# panel3.net
KiCad netlist of a schematic drawn in Altium Designer
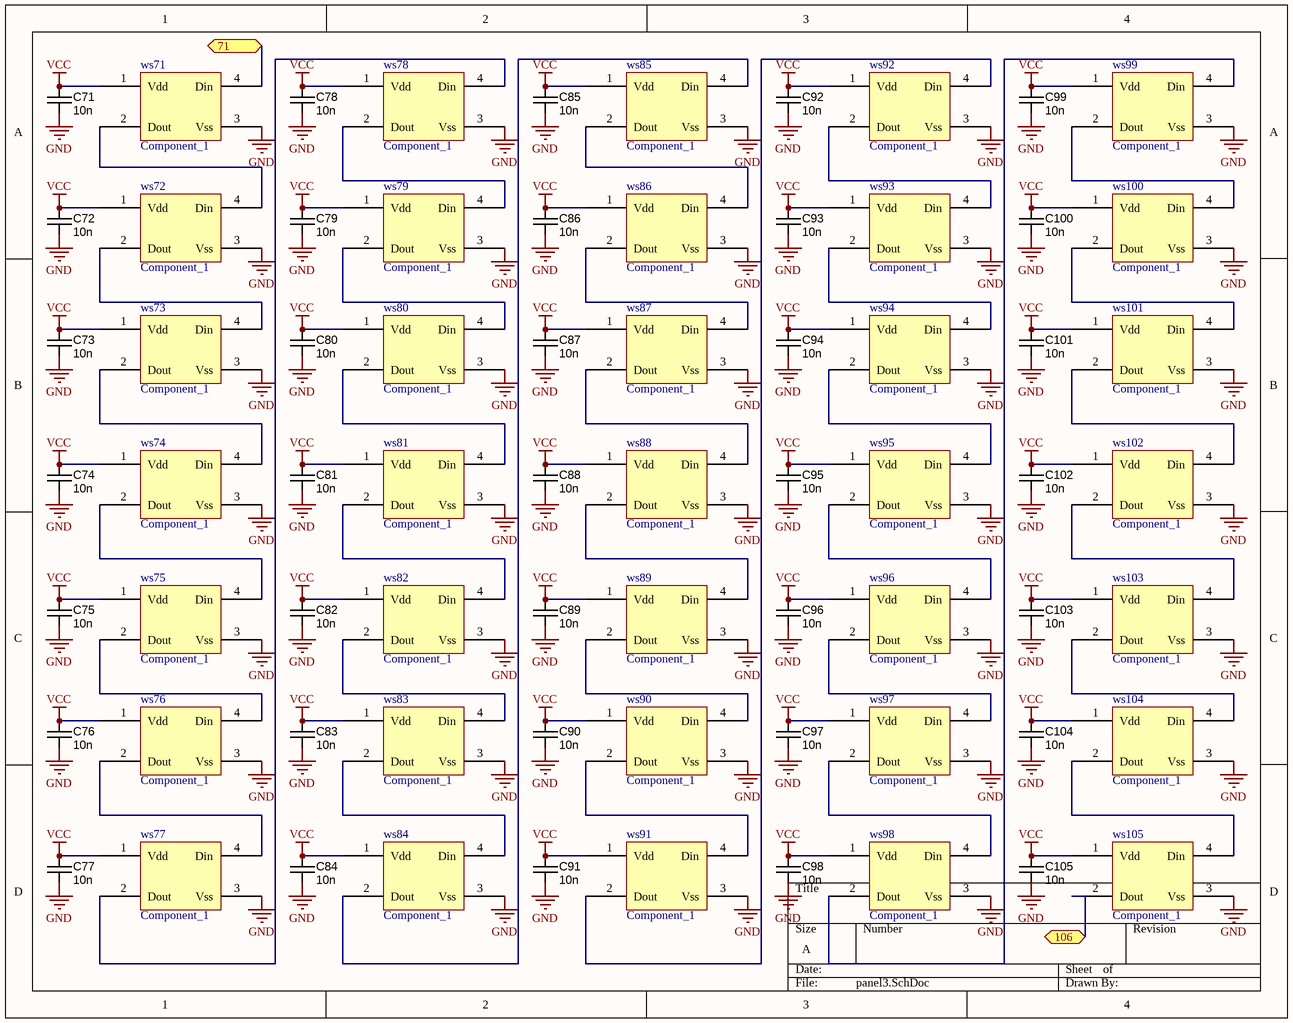
[diagram p0: panel3.SchDoc]

(export (version "E")
  (design (tool "Eeschema 10.0.6"))
  (components
    (comp (ref "C71")
      (value "10n")
      (footprint "CAPC1608X90N")
      (description "Capacitor SMD Cer 10nF 10% 100V X7R 0603")
      (fields
        (field (name "TOLERANCE") "±10%")
        (field (name "MANUFACTURER") "Murata Electronics North America")
      )
      (libsource (lib "PBL - Capacitors") (part "CAPC_10n_0603_X7R_100V_10%"))
    )
    (comp (ref "C72")
      (value "10n")
      (footprint "CAPC1608X90N")
      (description "Capacitor SMD Cer 10nF 10% 100V X7R 0603")
      (fields
        (field (name "TOLERANCE") "±10%")
        (field (name "MANUFACTURER") "Murata Electronics North America")
      )
      (libsource (lib "PBL - Capacitors") (part "CAPC_10n_0603_X7R_100V_10%"))
    )
    (comp (ref "C73")
      (value "10n")
      (footprint "CAPC1608X90N")
      (description "Capacitor SMD Cer 10nF 10% 100V X7R 0603")
      (fields
        (field (name "TOLERANCE") "±10%")
        (field (name "MANUFACTURER") "Murata Electronics North America")
      )
      (libsource (lib "PBL - Capacitors") (part "CAPC_10n_0603_X7R_100V_10%"))
    )
    (comp (ref "C74")
      (value "10n")
      (footprint "CAPC1608X90N")
      (description "Capacitor SMD Cer 10nF 10% 100V X7R 0603")
      (fields
        (field (name "TOLERANCE") "±10%")
        (field (name "MANUFACTURER") "Murata Electronics North America")
      )
      (libsource (lib "PBL - Capacitors") (part "CAPC_10n_0603_X7R_100V_10%"))
    )
    (comp (ref "C75")
      (value "10n")
      (footprint "CAPC1608X90N")
      (description "Capacitor SMD Cer 10nF 10% 100V X7R 0603")
      (fields
        (field (name "TOLERANCE") "±10%")
        (field (name "MANUFACTURER") "Murata Electronics North America")
      )
      (libsource (lib "PBL - Capacitors") (part "CAPC_10n_0603_X7R_100V_10%"))
    )
    (comp (ref "C76")
      (value "10n")
      (footprint "CAPC1608X90N")
      (description "Capacitor SMD Cer 10nF 10% 100V X7R 0603")
      (fields
        (field (name "TOLERANCE") "±10%")
        (field (name "MANUFACTURER") "Murata Electronics North America")
      )
      (libsource (lib "PBL - Capacitors") (part "CAPC_10n_0603_X7R_100V_10%"))
    )
    (comp (ref "C77")
      (value "10n")
      (footprint "CAPC1608X90N")
      (description "Capacitor SMD Cer 10nF 10% 100V X7R 0603")
      (fields
        (field (name "TOLERANCE") "±10%")
        (field (name "MANUFACTURER") "Murata Electronics North America")
      )
      (libsource (lib "PBL - Capacitors") (part "CAPC_10n_0603_X7R_100V_10%"))
    )
    (comp (ref "C78")
      (value "10n")
      (footprint "CAPC1608X90N")
      (description "Capacitor SMD Cer 10nF 10% 100V X7R 0603")
      (fields
        (field (name "TOLERANCE") "±10%")
        (field (name "MANUFACTURER") "Murata Electronics North America")
      )
      (libsource (lib "PBL - Capacitors") (part "CAPC_10n_0603_X7R_100V_10%"))
    )
    (comp (ref "C79")
      (value "10n")
      (footprint "CAPC1608X90N")
      (description "Capacitor SMD Cer 10nF 10% 100V X7R 0603")
      (fields
        (field (name "TOLERANCE") "±10%")
        (field (name "MANUFACTURER") "Murata Electronics North America")
      )
      (libsource (lib "PBL - Capacitors") (part "CAPC_10n_0603_X7R_100V_10%"))
    )
    (comp (ref "C80")
      (value "10n")
      (footprint "CAPC1608X90N")
      (description "Capacitor SMD Cer 10nF 10% 100V X7R 0603")
      (fields
        (field (name "TOLERANCE") "±10%")
        (field (name "MANUFACTURER") "Murata Electronics North America")
      )
      (libsource (lib "PBL - Capacitors") (part "CAPC_10n_0603_X7R_100V_10%"))
    )
    (comp (ref "C81")
      (value "10n")
      (footprint "CAPC1608X90N")
      (description "Capacitor SMD Cer 10nF 10% 100V X7R 0603")
      (fields
        (field (name "TOLERANCE") "±10%")
        (field (name "MANUFACTURER") "Murata Electronics North America")
      )
      (libsource (lib "PBL - Capacitors") (part "CAPC_10n_0603_X7R_100V_10%"))
    )
    (comp (ref "C82")
      (value "10n")
      (footprint "CAPC1608X90N")
      (description "Capacitor SMD Cer 10nF 10% 100V X7R 0603")
      (fields
        (field (name "TOLERANCE") "±10%")
        (field (name "MANUFACTURER") "Murata Electronics North America")
      )
      (libsource (lib "PBL - Capacitors") (part "CAPC_10n_0603_X7R_100V_10%"))
    )
    (comp (ref "C83")
      (value "10n")
      (footprint "CAPC1608X90N")
      (description "Capacitor SMD Cer 10nF 10% 100V X7R 0603")
      (fields
        (field (name "TOLERANCE") "±10%")
        (field (name "MANUFACTURER") "Murata Electronics North America")
      )
      (libsource (lib "PBL - Capacitors") (part "CAPC_10n_0603_X7R_100V_10%"))
    )
    (comp (ref "C84")
      (value "10n")
      (footprint "CAPC1608X90N")
      (description "Capacitor SMD Cer 10nF 10% 100V X7R 0603")
      (fields
        (field (name "TOLERANCE") "±10%")
        (field (name "MANUFACTURER") "Murata Electronics North America")
      )
      (libsource (lib "PBL - Capacitors") (part "CAPC_10n_0603_X7R_100V_10%"))
    )
    (comp (ref "C85")
      (value "10n")
      (footprint "CAPC1608X90N")
      (description "Capacitor SMD Cer 10nF 10% 100V X7R 0603")
      (fields
        (field (name "TOLERANCE") "±10%")
        (field (name "MANUFACTURER") "Murata Electronics North America")
      )
      (libsource (lib "PBL - Capacitors") (part "CAPC_10n_0603_X7R_100V_10%"))
    )
    (comp (ref "C86")
      (value "10n")
      (footprint "CAPC1608X90N")
      (description "Capacitor SMD Cer 10nF 10% 100V X7R 0603")
      (fields
        (field (name "TOLERANCE") "±10%")
        (field (name "MANUFACTURER") "Murata Electronics North America")
      )
      (libsource (lib "PBL - Capacitors") (part "CAPC_10n_0603_X7R_100V_10%"))
    )
    (comp (ref "C87")
      (value "10n")
      (footprint "CAPC1608X90N")
      (description "Capacitor SMD Cer 10nF 10% 100V X7R 0603")
      (fields
        (field (name "TOLERANCE") "±10%")
        (field (name "MANUFACTURER") "Murata Electronics North America")
      )
      (libsource (lib "PBL - Capacitors") (part "CAPC_10n_0603_X7R_100V_10%"))
    )
    (comp (ref "C88")
      (value "10n")
      (footprint "CAPC1608X90N")
      (description "Capacitor SMD Cer 10nF 10% 100V X7R 0603")
      (fields
        (field (name "TOLERANCE") "±10%")
        (field (name "MANUFACTURER") "Murata Electronics North America")
      )
      (libsource (lib "PBL - Capacitors") (part "CAPC_10n_0603_X7R_100V_10%"))
    )
    (comp (ref "C89")
      (value "10n")
      (footprint "CAPC1608X90N")
      (description "Capacitor SMD Cer 10nF 10% 100V X7R 0603")
      (fields
        (field (name "TOLERANCE") "±10%")
        (field (name "MANUFACTURER") "Murata Electronics North America")
      )
      (libsource (lib "PBL - Capacitors") (part "CAPC_10n_0603_X7R_100V_10%"))
    )
    (comp (ref "C90")
      (value "10n")
      (footprint "CAPC1608X90N")
      (description "Capacitor SMD Cer 10nF 10% 100V X7R 0603")
      (fields
        (field (name "TOLERANCE") "±10%")
        (field (name "MANUFACTURER") "Murata Electronics North America")
      )
      (libsource (lib "PBL - Capacitors") (part "CAPC_10n_0603_X7R_100V_10%"))
    )
    (comp (ref "C91")
      (value "10n")
      (footprint "CAPC1608X90N")
      (description "Capacitor SMD Cer 10nF 10% 100V X7R 0603")
      (fields
        (field (name "TOLERANCE") "±10%")
        (field (name "MANUFACTURER") "Murata Electronics North America")
      )
      (libsource (lib "PBL - Capacitors") (part "CAPC_10n_0603_X7R_100V_10%"))
    )
    (comp (ref "C92")
      (value "10n")
      (footprint "CAPC1608X90N")
      (description "Capacitor SMD Cer 10nF 10% 100V X7R 0603")
      (fields
        (field (name "TOLERANCE") "±10%")
        (field (name "MANUFACTURER") "Murata Electronics North America")
      )
      (libsource (lib "PBL - Capacitors") (part "CAPC_10n_0603_X7R_100V_10%"))
    )
    (comp (ref "C93")
      (value "10n")
      (footprint "CAPC1608X90N")
      (description "Capacitor SMD Cer 10nF 10% 100V X7R 0603")
      (fields
        (field (name "TOLERANCE") "±10%")
        (field (name "MANUFACTURER") "Murata Electronics North America")
      )
      (libsource (lib "PBL - Capacitors") (part "CAPC_10n_0603_X7R_100V_10%"))
    )
    (comp (ref "C94")
      (value "10n")
      (footprint "CAPC1608X90N")
      (description "Capacitor SMD Cer 10nF 10% 100V X7R 0603")
      (fields
        (field (name "TOLERANCE") "±10%")
        (field (name "MANUFACTURER") "Murata Electronics North America")
      )
      (libsource (lib "PBL - Capacitors") (part "CAPC_10n_0603_X7R_100V_10%"))
    )
    (comp (ref "C95")
      (value "10n")
      (footprint "CAPC1608X90N")
      (description "Capacitor SMD Cer 10nF 10% 100V X7R 0603")
      (fields
        (field (name "TOLERANCE") "±10%")
        (field (name "MANUFACTURER") "Murata Electronics North America")
      )
      (libsource (lib "PBL - Capacitors") (part "CAPC_10n_0603_X7R_100V_10%"))
    )
    (comp (ref "C96")
      (value "10n")
      (footprint "CAPC1608X90N")
      (description "Capacitor SMD Cer 10nF 10% 100V X7R 0603")
      (fields
        (field (name "TOLERANCE") "±10%")
        (field (name "MANUFACTURER") "Murata Electronics North America")
      )
      (libsource (lib "PBL - Capacitors") (part "CAPC_10n_0603_X7R_100V_10%"))
    )
    (comp (ref "C97")
      (value "10n")
      (footprint "CAPC1608X90N")
      (description "Capacitor SMD Cer 10nF 10% 100V X7R 0603")
      (fields
        (field (name "TOLERANCE") "±10%")
        (field (name "MANUFACTURER") "Murata Electronics North America")
      )
      (libsource (lib "PBL - Capacitors") (part "CAPC_10n_0603_X7R_100V_10%"))
    )
    (comp (ref "C98")
      (value "10n")
      (footprint "CAPC1608X90N")
      (description "Capacitor SMD Cer 10nF 10% 100V X7R 0603")
      (fields
        (field (name "TOLERANCE") "±10%")
        (field (name "MANUFACTURER") "Murata Electronics North America")
      )
      (libsource (lib "PBL - Capacitors") (part "CAPC_10n_0603_X7R_100V_10%"))
    )
    (comp (ref "C99")
      (value "10n")
      (footprint "CAPC1608X90N")
      (description "Capacitor SMD Cer 10nF 10% 100V X7R 0603")
      (fields
        (field (name "TOLERANCE") "±10%")
        (field (name "MANUFACTURER") "Murata Electronics North America")
      )
      (libsource (lib "PBL - Capacitors") (part "CAPC_10n_0603_X7R_100V_10%"))
    )
    (comp (ref "C100")
      (value "10n")
      (footprint "CAPC1608X90N")
      (description "Capacitor SMD Cer 10nF 10% 100V X7R 0603")
      (fields
        (field (name "TOLERANCE") "±10%")
        (field (name "MANUFACTURER") "Murata Electronics North America")
      )
      (libsource (lib "PBL - Capacitors") (part "CAPC_10n_0603_X7R_100V_10%"))
    )
    (comp (ref "C101")
      (value "10n")
      (footprint "CAPC1608X90N")
      (description "Capacitor SMD Cer 10nF 10% 100V X7R 0603")
      (fields
        (field (name "TOLERANCE") "±10%")
        (field (name "MANUFACTURER") "Murata Electronics North America")
      )
      (libsource (lib "PBL - Capacitors") (part "CAPC_10n_0603_X7R_100V_10%"))
    )
    (comp (ref "C102")
      (value "10n")
      (footprint "CAPC1608X90N")
      (description "Capacitor SMD Cer 10nF 10% 100V X7R 0603")
      (fields
        (field (name "TOLERANCE") "±10%")
        (field (name "MANUFACTURER") "Murata Electronics North America")
      )
      (libsource (lib "PBL - Capacitors") (part "CAPC_10n_0603_X7R_100V_10%"))
    )
    (comp (ref "C103")
      (value "10n")
      (footprint "CAPC1608X90N")
      (description "Capacitor SMD Cer 10nF 10% 100V X7R 0603")
      (fields
        (field (name "TOLERANCE") "±10%")
        (field (name "MANUFACTURER") "Murata Electronics North America")
      )
      (libsource (lib "PBL - Capacitors") (part "CAPC_10n_0603_X7R_100V_10%"))
    )
    (comp (ref "C104")
      (value "10n")
      (footprint "CAPC1608X90N")
      (description "Capacitor SMD Cer 10nF 10% 100V X7R 0603")
      (fields
        (field (name "TOLERANCE") "±10%")
        (field (name "MANUFACTURER") "Murata Electronics North America")
      )
      (libsource (lib "PBL - Capacitors") (part "CAPC_10n_0603_X7R_100V_10%"))
    )
    (comp (ref "C105")
      (value "10n")
      (footprint "CAPC1608X90N")
      (description "Capacitor SMD Cer 10nF 10% 100V X7R 0603")
      (fields
        (field (name "TOLERANCE") "±10%")
        (field (name "MANUFACTURER") "Murata Electronics North America")
      )
      (libsource (lib "PBL - Capacitors") (part "CAPC_10n_0603_X7R_100V_10%"))
    )
    (comp (ref "ws71")
      (value "Component_1")
      (footprint "SOP4")
      (libsource (lib "ws2812b") (part "Component_1"))
    )
    (comp (ref "ws72")
      (value "Component_1")
      (footprint "SOP4")
      (libsource (lib "ws2812b") (part "Component_1"))
    )
    (comp (ref "ws73")
      (value "Component_1")
      (footprint "SOP4")
      (libsource (lib "ws2812b") (part "Component_1"))
    )
    (comp (ref "ws74")
      (value "Component_1")
      (footprint "SOP4")
      (libsource (lib "ws2812b") (part "Component_1"))
    )
    (comp (ref "ws75")
      (value "Component_1")
      (footprint "SOP4")
      (libsource (lib "ws2812b") (part "Component_1"))
    )
    (comp (ref "ws76")
      (value "Component_1")
      (footprint "SOP4")
      (libsource (lib "ws2812b") (part "Component_1"))
    )
    (comp (ref "ws77")
      (value "Component_1")
      (footprint "SOP4")
      (libsource (lib "ws2812b") (part "Component_1"))
    )
    (comp (ref "ws78")
      (value "Component_1")
      (footprint "SOP4")
      (libsource (lib "ws2812b") (part "Component_1"))
    )
    (comp (ref "ws79")
      (value "Component_1")
      (footprint "SOP4")
      (libsource (lib "ws2812b") (part "Component_1"))
    )
    (comp (ref "ws80")
      (value "Component_1")
      (footprint "SOP4")
      (libsource (lib "ws2812b") (part "Component_1"))
    )
    (comp (ref "ws81")
      (value "Component_1")
      (footprint "SOP4")
      (libsource (lib "ws2812b") (part "Component_1"))
    )
    (comp (ref "ws82")
      (value "Component_1")
      (footprint "SOP4")
      (libsource (lib "ws2812b") (part "Component_1"))
    )
    (comp (ref "ws83")
      (value "Component_1")
      (footprint "SOP4")
      (libsource (lib "ws2812b") (part "Component_1"))
    )
    (comp (ref "ws84")
      (value "Component_1")
      (footprint "SOP4")
      (libsource (lib "ws2812b") (part "Component_1"))
    )
    (comp (ref "ws85")
      (value "Component_1")
      (footprint "SOP4")
      (libsource (lib "ws2812b") (part "Component_1"))
    )
    (comp (ref "ws86")
      (value "Component_1")
      (footprint "SOP4")
      (libsource (lib "ws2812b") (part "Component_1"))
    )
    (comp (ref "ws87")
      (value "Component_1")
      (footprint "SOP4")
      (libsource (lib "ws2812b") (part "Component_1"))
    )
    (comp (ref "ws88")
      (value "Component_1")
      (footprint "SOP4")
      (libsource (lib "ws2812b") (part "Component_1"))
    )
    (comp (ref "ws89")
      (value "Component_1")
      (footprint "SOP4")
      (libsource (lib "ws2812b") (part "Component_1"))
    )
    (comp (ref "ws90")
      (value "Component_1")
      (footprint "SOP4")
      (libsource (lib "ws2812b") (part "Component_1"))
    )
    (comp (ref "ws91")
      (value "Component_1")
      (footprint "SOP4")
      (libsource (lib "ws2812b") (part "Component_1"))
    )
    (comp (ref "ws92")
      (value "Component_1")
      (footprint "SOP4")
      (libsource (lib "ws2812b") (part "Component_1"))
    )
    (comp (ref "ws93")
      (value "Component_1")
      (footprint "SOP4")
      (libsource (lib "ws2812b") (part "Component_1"))
    )
    (comp (ref "ws94")
      (value "Component_1")
      (footprint "SOP4")
      (libsource (lib "ws2812b") (part "Component_1"))
    )
    (comp (ref "ws95")
      (value "Component_1")
      (footprint "SOP4")
      (libsource (lib "ws2812b") (part "Component_1"))
    )
    (comp (ref "ws96")
      (value "Component_1")
      (footprint "SOP4")
      (libsource (lib "ws2812b") (part "Component_1"))
    )
    (comp (ref "ws97")
      (value "Component_1")
      (footprint "SOP4")
      (libsource (lib "ws2812b") (part "Component_1"))
    )
    (comp (ref "ws98")
      (value "Component_1")
      (footprint "SOP4")
      (libsource (lib "ws2812b") (part "Component_1"))
    )
    (comp (ref "ws99")
      (value "Component_1")
      (footprint "SOP4")
      (libsource (lib "ws2812b") (part "Component_1"))
    )
    (comp (ref "ws100")
      (value "Component_1")
      (footprint "SOP4")
      (libsource (lib "ws2812b") (part "Component_1"))
    )
    (comp (ref "ws101")
      (value "Component_1")
      (footprint "SOP4")
      (libsource (lib "ws2812b") (part "Component_1"))
    )
    (comp (ref "ws102")
      (value "Component_1")
      (footprint "SOP4")
      (libsource (lib "ws2812b") (part "Component_1"))
    )
    (comp (ref "ws103")
      (value "Component_1")
      (footprint "SOP4")
      (libsource (lib "ws2812b") (part "Component_1"))
    )
    (comp (ref "ws104")
      (value "Component_1")
      (footprint "SOP4")
      (libsource (lib "ws2812b") (part "Component_1"))
    )
    (comp (ref "ws105")
      (value "Component_1")
      (footprint "SOP4")
      (libsource (lib "ws2812b") (part "Component_1"))
    )
  )
  (nets
    (net (code "1") (name "/71") (class "Default")
      (node (ref "ws71") (pin "4") (pinfunction "Din_4") (pintype "passive"))
    )
    (net (code "2") (name "/106") (class "Default")
      (node (ref "ws105") (pin "2") (pinfunction "Dout_2") (pintype "passive"))
    )
    (net (code "3") (name "GND") (class "Default")
      (node (ref "C100") (pin "2") (pintype "passive"))
      (node (ref "C101") (pin "2") (pintype "passive"))
      (node (ref "C102") (pin "2") (pintype "passive"))
      (node (ref "C103") (pin "2") (pintype "passive"))
      (node (ref "C104") (pin "2") (pintype "passive"))
      (node (ref "C105") (pin "2") (pintype "passive"))
      (node (ref "C71") (pin "2") (pintype "passive"))
      (node (ref "C72") (pin "2") (pintype "passive"))
      (node (ref "C73") (pin "2") (pintype "passive"))
      (node (ref "C74") (pin "2") (pintype "passive"))
      (node (ref "C75") (pin "2") (pintype "passive"))
      (node (ref "C76") (pin "2") (pintype "passive"))
      (node (ref "C77") (pin "2") (pintype "passive"))
      (node (ref "C78") (pin "2") (pintype "passive"))
      (node (ref "C79") (pin "2") (pintype "passive"))
      (node (ref "C80") (pin "2") (pintype "passive"))
      (node (ref "C81") (pin "2") (pintype "passive"))
      (node (ref "C82") (pin "2") (pintype "passive"))
      (node (ref "C83") (pin "2") (pintype "passive"))
      (node (ref "C84") (pin "2") (pintype "passive"))
      (node (ref "C85") (pin "2") (pintype "passive"))
      (node (ref "C86") (pin "2") (pintype "passive"))
      (node (ref "C87") (pin "2") (pintype "passive"))
      (node (ref "C88") (pin "2") (pintype "passive"))
      (node (ref "C89") (pin "2") (pintype "passive"))
      (node (ref "C90") (pin "2") (pintype "passive"))
      (node (ref "C91") (pin "2") (pintype "passive"))
      (node (ref "C92") (pin "2") (pintype "passive"))
      (node (ref "C93") (pin "2") (pintype "passive"))
      (node (ref "C94") (pin "2") (pintype "passive"))
      (node (ref "C95") (pin "2") (pintype "passive"))
      (node (ref "C96") (pin "2") (pintype "passive"))
      (node (ref "C97") (pin "2") (pintype "passive"))
      (node (ref "C98") (pin "2") (pintype "passive"))
      (node (ref "C99") (pin "2") (pintype "passive"))
      (node (ref "ws100") (pin "3") (pinfunction "Vss_3") (pintype "passive"))
      (node (ref "ws101") (pin "3") (pinfunction "Vss_3") (pintype "passive"))
      (node (ref "ws102") (pin "3") (pinfunction "Vss_3") (pintype "passive"))
      (node (ref "ws103") (pin "3") (pinfunction "Vss_3") (pintype "passive"))
      (node (ref "ws104") (pin "3") (pinfunction "Vss_3") (pintype "passive"))
      (node (ref "ws105") (pin "3") (pinfunction "Vss_3") (pintype "passive"))
      (node (ref "ws71") (pin "3") (pinfunction "Vss_3") (pintype "passive"))
      (node (ref "ws72") (pin "3") (pinfunction "Vss_3") (pintype "passive"))
      (node (ref "ws73") (pin "3") (pinfunction "Vss_3") (pintype "passive"))
      (node (ref "ws74") (pin "3") (pinfunction "Vss_3") (pintype "passive"))
      (node (ref "ws75") (pin "3") (pinfunction "Vss_3") (pintype "passive"))
      (node (ref "ws76") (pin "3") (pinfunction "Vss_3") (pintype "passive"))
      (node (ref "ws77") (pin "3") (pinfunction "Vss_3") (pintype "passive"))
      (node (ref "ws78") (pin "3") (pinfunction "Vss_3") (pintype "passive"))
      (node (ref "ws79") (pin "3") (pinfunction "Vss_3") (pintype "passive"))
      (node (ref "ws80") (pin "3") (pinfunction "Vss_3") (pintype "passive"))
      (node (ref "ws81") (pin "3") (pinfunction "Vss_3") (pintype "passive"))
      (node (ref "ws82") (pin "3") (pinfunction "Vss_3") (pintype "passive"))
      (node (ref "ws83") (pin "3") (pinfunction "Vss_3") (pintype "passive"))
      (node (ref "ws84") (pin "3") (pinfunction "Vss_3") (pintype "passive"))
      (node (ref "ws85") (pin "3") (pinfunction "Vss_3") (pintype "passive"))
      (node (ref "ws86") (pin "3") (pinfunction "Vss_3") (pintype "passive"))
      (node (ref "ws87") (pin "3") (pinfunction "Vss_3") (pintype "passive"))
      (node (ref "ws88") (pin "3") (pinfunction "Vss_3") (pintype "passive"))
      (node (ref "ws89") (pin "3") (pinfunction "Vss_3") (pintype "passive"))
      (node (ref "ws90") (pin "3") (pinfunction "Vss_3") (pintype "passive"))
      (node (ref "ws91") (pin "3") (pinfunction "Vss_3") (pintype "passive"))
      (node (ref "ws92") (pin "3") (pinfunction "Vss_3") (pintype "passive"))
      (node (ref "ws93") (pin "3") (pinfunction "Vss_3") (pintype "passive"))
      (node (ref "ws94") (pin "3") (pinfunction "Vss_3") (pintype "passive"))
      (node (ref "ws95") (pin "3") (pinfunction "Vss_3") (pintype "passive"))
      (node (ref "ws96") (pin "3") (pinfunction "Vss_3") (pintype "passive"))
      (node (ref "ws97") (pin "3") (pinfunction "Vss_3") (pintype "passive"))
      (node (ref "ws98") (pin "3") (pinfunction "Vss_3") (pintype "passive"))
      (node (ref "ws99") (pin "3") (pinfunction "Vss_3") (pintype "passive"))
    )
    (net (code "4") (name "Net-(ws71-Dout)") (class "Default")
      (node (ref "ws71") (pin "2") (pinfunction "Dout_2") (pintype "passive"))
      (node (ref "ws72") (pin "4") (pinfunction "Din_4") (pintype "passive"))
    )
    (net (code "5") (name "Net-(ws72-Dout)") (class "Default")
      (node (ref "ws72") (pin "2") (pinfunction "Dout_2") (pintype "passive"))
      (node (ref "ws73") (pin "4") (pinfunction "Din_4") (pintype "passive"))
    )
    (net (code "6") (name "Net-(ws73-Dout)") (class "Default")
      (node (ref "ws73") (pin "2") (pinfunction "Dout_2") (pintype "passive"))
      (node (ref "ws74") (pin "4") (pinfunction "Din_4") (pintype "passive"))
    )
    (net (code "7") (name "Net-(ws74-Dout)") (class "Default")
      (node (ref "ws74") (pin "2") (pinfunction "Dout_2") (pintype "passive"))
      (node (ref "ws75") (pin "4") (pinfunction "Din_4") (pintype "passive"))
    )
    (net (code "8") (name "Net-(ws75-Dout)") (class "Default")
      (node (ref "ws75") (pin "2") (pinfunction "Dout_2") (pintype "passive"))
      (node (ref "ws76") (pin "4") (pinfunction "Din_4") (pintype "passive"))
    )
    (net (code "9") (name "Net-(ws76-Dout)") (class "Default")
      (node (ref "ws76") (pin "2") (pinfunction "Dout_2") (pintype "passive"))
      (node (ref "ws77") (pin "4") (pinfunction "Din_4") (pintype "passive"))
    )
    (net (code "10") (name "Net-(ws77-Dout)") (class "Default")
      (node (ref "ws77") (pin "2") (pinfunction "Dout_2") (pintype "passive"))
      (node (ref "ws78") (pin "4") (pinfunction "Din_4") (pintype "passive"))
    )
    (net (code "11") (name "Net-(ws78-Dout)") (class "Default")
      (node (ref "ws78") (pin "2") (pinfunction "Dout_2") (pintype "passive"))
      (node (ref "ws79") (pin "4") (pinfunction "Din_4") (pintype "passive"))
    )
    (net (code "12") (name "Net-(ws79-Dout)") (class "Default")
      (node (ref "ws79") (pin "2") (pinfunction "Dout_2") (pintype "passive"))
      (node (ref "ws80") (pin "4") (pinfunction "Din_4") (pintype "passive"))
    )
    (net (code "13") (name "Net-(ws80-Dout)") (class "Default")
      (node (ref "ws80") (pin "2") (pinfunction "Dout_2") (pintype "passive"))
      (node (ref "ws81") (pin "4") (pinfunction "Din_4") (pintype "passive"))
    )
    (net (code "14") (name "Net-(ws81-Dout)") (class "Default")
      (node (ref "ws81") (pin "2") (pinfunction "Dout_2") (pintype "passive"))
      (node (ref "ws82") (pin "4") (pinfunction "Din_4") (pintype "passive"))
    )
    (net (code "15") (name "Net-(ws82-Dout)") (class "Default")
      (node (ref "ws82") (pin "2") (pinfunction "Dout_2") (pintype "passive"))
      (node (ref "ws83") (pin "4") (pinfunction "Din_4") (pintype "passive"))
    )
    (net (code "16") (name "Net-(ws83-Dout)") (class "Default")
      (node (ref "ws83") (pin "2") (pinfunction "Dout_2") (pintype "passive"))
      (node (ref "ws84") (pin "4") (pinfunction "Din_4") (pintype "passive"))
    )
    (net (code "17") (name "Net-(ws84-Dout)") (class "Default")
      (node (ref "ws84") (pin "2") (pinfunction "Dout_2") (pintype "passive"))
      (node (ref "ws85") (pin "4") (pinfunction "Din_4") (pintype "passive"))
    )
    (net (code "18") (name "Net-(ws85-Dout)") (class "Default")
      (node (ref "ws85") (pin "2") (pinfunction "Dout_2") (pintype "passive"))
      (node (ref "ws86") (pin "4") (pinfunction "Din_4") (pintype "passive"))
    )
    (net (code "19") (name "Net-(ws86-Dout)") (class "Default")
      (node (ref "ws86") (pin "2") (pinfunction "Dout_2") (pintype "passive"))
      (node (ref "ws87") (pin "4") (pinfunction "Din_4") (pintype "passive"))
    )
    (net (code "20") (name "Net-(ws87-Dout)") (class "Default")
      (node (ref "ws87") (pin "2") (pinfunction "Dout_2") (pintype "passive"))
      (node (ref "ws88") (pin "4") (pinfunction "Din_4") (pintype "passive"))
    )
    (net (code "21") (name "Net-(ws88-Dout)") (class "Default")
      (node (ref "ws88") (pin "2") (pinfunction "Dout_2") (pintype "passive"))
      (node (ref "ws89") (pin "4") (pinfunction "Din_4") (pintype "passive"))
    )
    (net (code "22") (name "Net-(ws89-Dout)") (class "Default")
      (node (ref "ws89") (pin "2") (pinfunction "Dout_2") (pintype "passive"))
      (node (ref "ws90") (pin "4") (pinfunction "Din_4") (pintype "passive"))
    )
    (net (code "23") (name "Net-(ws90-Dout)") (class "Default")
      (node (ref "ws90") (pin "2") (pinfunction "Dout_2") (pintype "passive"))
      (node (ref "ws91") (pin "4") (pinfunction "Din_4") (pintype "passive"))
    )
    (net (code "24") (name "Net-(ws91-Dout)") (class "Default")
      (node (ref "ws91") (pin "2") (pinfunction "Dout_2") (pintype "passive"))
      (node (ref "ws92") (pin "4") (pinfunction "Din_4") (pintype "passive"))
    )
    (net (code "25") (name "Net-(ws92-Dout)") (class "Default")
      (node (ref "ws92") (pin "2") (pinfunction "Dout_2") (pintype "passive"))
      (node (ref "ws93") (pin "4") (pinfunction "Din_4") (pintype "passive"))
    )
    (net (code "26") (name "Net-(ws93-Dout)") (class "Default")
      (node (ref "ws93") (pin "2") (pinfunction "Dout_2") (pintype "passive"))
      (node (ref "ws94") (pin "4") (pinfunction "Din_4") (pintype "passive"))
    )
    (net (code "27") (name "Net-(ws94-Dout)") (class "Default")
      (node (ref "ws94") (pin "2") (pinfunction "Dout_2") (pintype "passive"))
      (node (ref "ws95") (pin "4") (pinfunction "Din_4") (pintype "passive"))
    )
    (net (code "28") (name "Net-(ws95-Dout)") (class "Default")
      (node (ref "ws95") (pin "2") (pinfunction "Dout_2") (pintype "passive"))
      (node (ref "ws96") (pin "4") (pinfunction "Din_4") (pintype "passive"))
    )
    (net (code "29") (name "Net-(ws96-Dout)") (class "Default")
      (node (ref "ws96") (pin "2") (pinfunction "Dout_2") (pintype "passive"))
      (node (ref "ws97") (pin "4") (pinfunction "Din_4") (pintype "passive"))
    )
    (net (code "30") (name "Net-(ws97-Dout)") (class "Default")
      (node (ref "ws97") (pin "2") (pinfunction "Dout_2") (pintype "passive"))
      (node (ref "ws98") (pin "4") (pinfunction "Din_4") (pintype "passive"))
    )
    (net (code "31") (name "Net-(ws98-Dout)") (class "Default")
      (node (ref "ws98") (pin "2") (pinfunction "Dout_2") (pintype "passive"))
      (node (ref "ws99") (pin "4") (pinfunction "Din_4") (pintype "passive"))
    )
    (net (code "32") (name "Net-(ws100-Din)") (class "Default")
      (node (ref "ws100") (pin "4") (pinfunction "Din_4") (pintype "passive"))
      (node (ref "ws99") (pin "2") (pinfunction "Dout_2") (pintype "passive"))
    )
    (net (code "33") (name "Net-(ws100-Dout)") (class "Default")
      (node (ref "ws100") (pin "2") (pinfunction "Dout_2") (pintype "passive"))
      (node (ref "ws101") (pin "4") (pinfunction "Din_4") (pintype "passive"))
    )
    (net (code "34") (name "Net-(ws101-Dout)") (class "Default")
      (node (ref "ws101") (pin "2") (pinfunction "Dout_2") (pintype "passive"))
      (node (ref "ws102") (pin "4") (pinfunction "Din_4") (pintype "passive"))
    )
    (net (code "35") (name "Net-(ws102-Dout)") (class "Default")
      (node (ref "ws102") (pin "2") (pinfunction "Dout_2") (pintype "passive"))
      (node (ref "ws103") (pin "4") (pinfunction "Din_4") (pintype "passive"))
    )
    (net (code "36") (name "Net-(ws103-Dout)") (class "Default")
      (node (ref "ws103") (pin "2") (pinfunction "Dout_2") (pintype "passive"))
      (node (ref "ws104") (pin "4") (pinfunction "Din_4") (pintype "passive"))
    )
    (net (code "37") (name "Net-(ws104-Dout)") (class "Default")
      (node (ref "ws104") (pin "2") (pinfunction "Dout_2") (pintype "passive"))
      (node (ref "ws105") (pin "4") (pinfunction "Din_4") (pintype "passive"))
    )
    (net (code "38") (name "VCC") (class "Default")
      (node (ref "C100") (pin "1") (pintype "passive"))
      (node (ref "C101") (pin "1") (pintype "passive"))
      (node (ref "C102") (pin "1") (pintype "passive"))
      (node (ref "C103") (pin "1") (pintype "passive"))
      (node (ref "C104") (pin "1") (pintype "passive"))
      (node (ref "C105") (pin "1") (pintype "passive"))
      (node (ref "C71") (pin "1") (pintype "passive"))
      (node (ref "C72") (pin "1") (pintype "passive"))
      (node (ref "C73") (pin "1") (pintype "passive"))
      (node (ref "C74") (pin "1") (pintype "passive"))
      (node (ref "C75") (pin "1") (pintype "passive"))
      (node (ref "C76") (pin "1") (pintype "passive"))
      (node (ref "C77") (pin "1") (pintype "passive"))
      (node (ref "C78") (pin "1") (pintype "passive"))
      (node (ref "C79") (pin "1") (pintype "passive"))
      (node (ref "C80") (pin "1") (pintype "passive"))
      (node (ref "C81") (pin "1") (pintype "passive"))
      (node (ref "C82") (pin "1") (pintype "passive"))
      (node (ref "C83") (pin "1") (pintype "passive"))
      (node (ref "C84") (pin "1") (pintype "passive"))
      (node (ref "C85") (pin "1") (pintype "passive"))
      (node (ref "C86") (pin "1") (pintype "passive"))
      (node (ref "C87") (pin "1") (pintype "passive"))
      (node (ref "C88") (pin "1") (pintype "passive"))
      (node (ref "C89") (pin "1") (pintype "passive"))
      (node (ref "C90") (pin "1") (pintype "passive"))
      (node (ref "C91") (pin "1") (pintype "passive"))
      (node (ref "C92") (pin "1") (pintype "passive"))
      (node (ref "C93") (pin "1") (pintype "passive"))
      (node (ref "C94") (pin "1") (pintype "passive"))
      (node (ref "C95") (pin "1") (pintype "passive"))
      (node (ref "C96") (pin "1") (pintype "passive"))
      (node (ref "C97") (pin "1") (pintype "passive"))
      (node (ref "C98") (pin "1") (pintype "passive"))
      (node (ref "C99") (pin "1") (pintype "passive"))
      (node (ref "ws100") (pin "1") (pinfunction "Vdd_1") (pintype "passive"))
      (node (ref "ws101") (pin "1") (pinfunction "Vdd_1") (pintype "passive"))
      (node (ref "ws102") (pin "1") (pinfunction "Vdd_1") (pintype "passive"))
      (node (ref "ws103") (pin "1") (pinfunction "Vdd_1") (pintype "passive"))
      (node (ref "ws104") (pin "1") (pinfunction "Vdd_1") (pintype "passive"))
      (node (ref "ws105") (pin "1") (pinfunction "Vdd_1") (pintype "passive"))
      (node (ref "ws71") (pin "1") (pinfunction "Vdd_1") (pintype "passive"))
      (node (ref "ws72") (pin "1") (pinfunction "Vdd_1") (pintype "passive"))
      (node (ref "ws73") (pin "1") (pinfunction "Vdd_1") (pintype "passive"))
      (node (ref "ws74") (pin "1") (pinfunction "Vdd_1") (pintype "passive"))
      (node (ref "ws75") (pin "1") (pinfunction "Vdd_1") (pintype "passive"))
      (node (ref "ws76") (pin "1") (pinfunction "Vdd_1") (pintype "passive"))
      (node (ref "ws77") (pin "1") (pinfunction "Vdd_1") (pintype "passive"))
      (node (ref "ws78") (pin "1") (pinfunction "Vdd_1") (pintype "passive"))
      (node (ref "ws79") (pin "1") (pinfunction "Vdd_1") (pintype "passive"))
      (node (ref "ws80") (pin "1") (pinfunction "Vdd_1") (pintype "passive"))
      (node (ref "ws81") (pin "1") (pinfunction "Vdd_1") (pintype "passive"))
      (node (ref "ws82") (pin "1") (pinfunction "Vdd_1") (pintype "passive"))
      (node (ref "ws83") (pin "1") (pinfunction "Vdd_1") (pintype "passive"))
      (node (ref "ws84") (pin "1") (pinfunction "Vdd_1") (pintype "passive"))
      (node (ref "ws85") (pin "1") (pinfunction "Vdd_1") (pintype "passive"))
      (node (ref "ws86") (pin "1") (pinfunction "Vdd_1") (pintype "passive"))
      (node (ref "ws87") (pin "1") (pinfunction "Vdd_1") (pintype "passive"))
      (node (ref "ws88") (pin "1") (pinfunction "Vdd_1") (pintype "passive"))
      (node (ref "ws89") (pin "1") (pinfunction "Vdd_1") (pintype "passive"))
      (node (ref "ws90") (pin "1") (pinfunction "Vdd_1") (pintype "passive"))
      (node (ref "ws91") (pin "1") (pinfunction "Vdd_1") (pintype "passive"))
      (node (ref "ws92") (pin "1") (pinfunction "Vdd_1") (pintype "passive"))
      (node (ref "ws93") (pin "1") (pinfunction "Vdd_1") (pintype "passive"))
      (node (ref "ws94") (pin "1") (pinfunction "Vdd_1") (pintype "passive"))
      (node (ref "ws95") (pin "1") (pinfunction "Vdd_1") (pintype "passive"))
      (node (ref "ws96") (pin "1") (pinfunction "Vdd_1") (pintype "passive"))
      (node (ref "ws97") (pin "1") (pinfunction "Vdd_1") (pintype "passive"))
      (node (ref "ws98") (pin "1") (pinfunction "Vdd_1") (pintype "passive"))
      (node (ref "ws99") (pin "1") (pinfunction "Vdd_1") (pintype "passive"))
    )
  )
)
